# SD_SC.net
KiCad netlist of a schematic drawn in Altium Designer
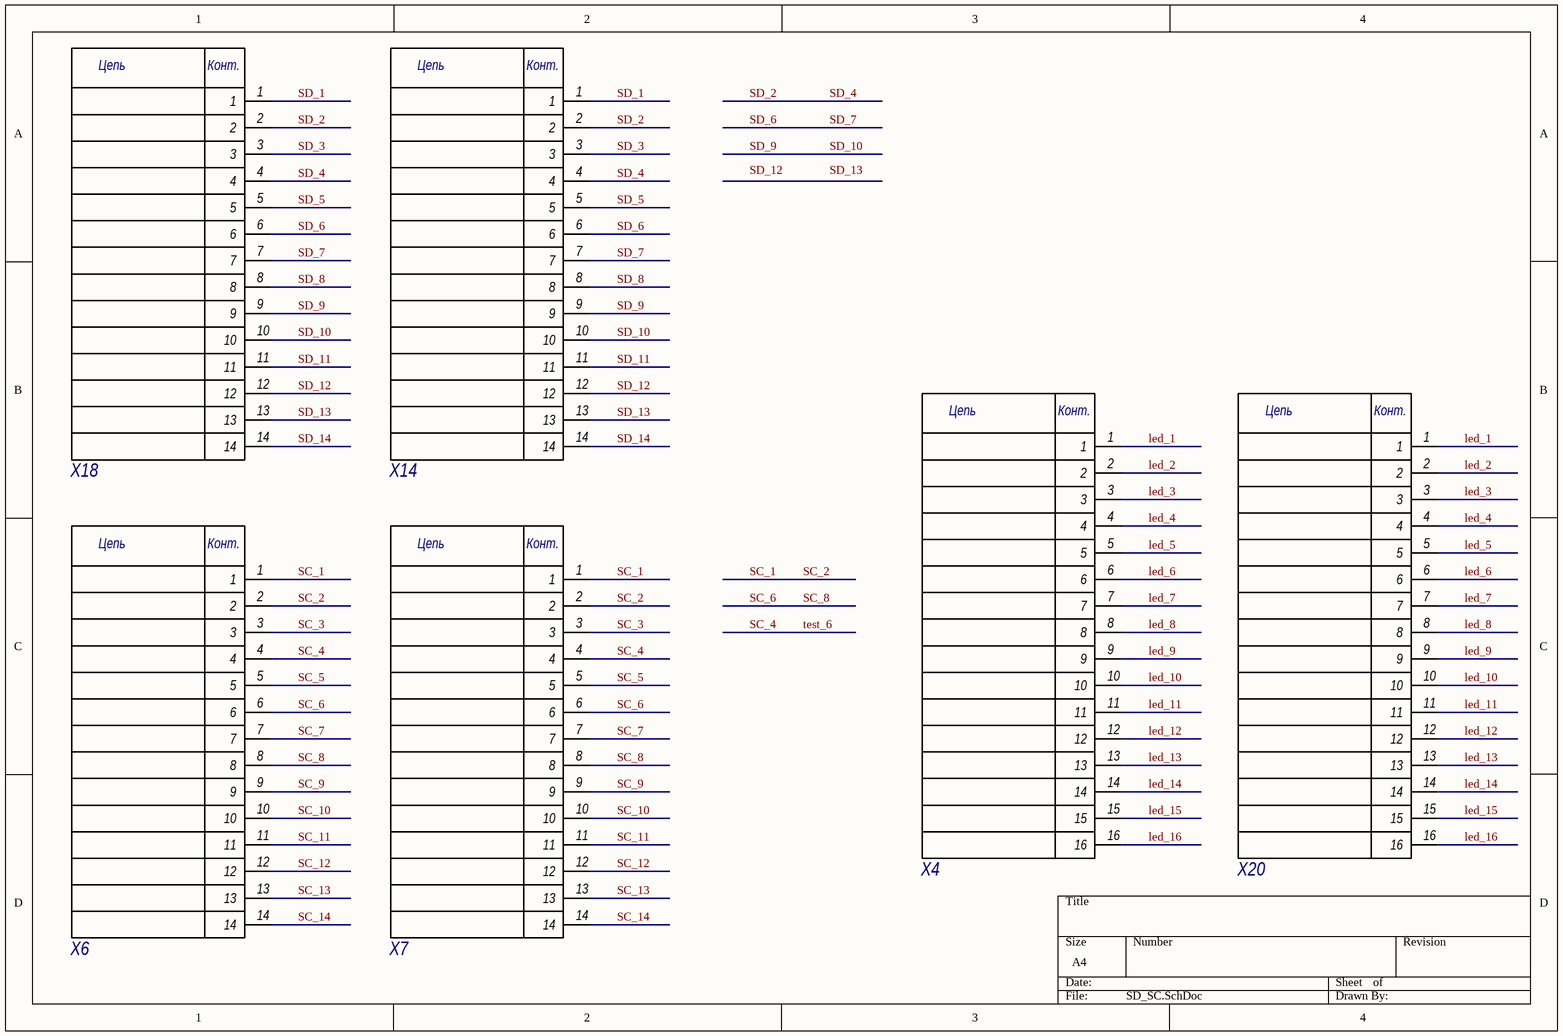
[diagram p0: SD_SC.SchDoc]

(export (version "E")
  (design (tool "Eeschema 10.0.6"))
  (components
    (comp (ref "X4")
      (value "PLD-16")
      (footprint "PLD-16")
      (description "штыри на плату")
      (libsource (lib "DatabaseSVN") (part "CON_16"))
    )
    (comp (ref "X6")
      (value "2x7")
      (footprint "87832_1420")
      (description "Connector Header Surface Mount 14 position 0.079\" (2.00mm)")
      (fields (field (name "PARTNUMBER") "87832-1420") (field (name "MANUFACTURER") "Molex"))
      (libsource (lib "DatabaseSVN") (part "CON_14"))
    )
    (comp (ref "X7")
      (value "PLD-14")
      (footprint "PLD-14")
      (description "штыри на плату")
      (libsource (lib "DatabaseSVN") (part "CON_14"))
    )
    (comp (ref "X14")
      (value "PLD-14")
      (footprint "PLD-14")
      (description "штыри на плату")
      (libsource (lib "DatabaseSVN") (part "CON_14"))
    )
    (comp (ref "X18")
      (value "2x7")
      (footprint "87832_1420")
      (description "Connector Header Surface Mount 14 position 0.079\" (2.00mm)")
      (fields (field (name "PARTNUMBER") "87832-1420") (field (name "MANUFACTURER") "Molex"))
      (libsource (lib "DatabaseSVN") (part "CON_14"))
    )
    (comp (ref "X20")
      (value "2x7")
      (footprint "87832_1620")
      (description "Connector Header Surface Mount 16 position 0.079\" (2.00mm)")
      (fields (field (name "PARTNUMBER") "87832-1620") (field (name "MANUFACTURER") "Molex"))
      (libsource (lib "DatabaseSVN") (part "CON_16"))
    )
  )
  (nets
    (net (code "1") (name "/SC_1") (class "Default")
      (node (ref "X6") (pin "1") (pinfunction "1_1") (pintype "passive"))
      (node (ref "X6") (pin "2") (pinfunction "2_2") (pintype "passive"))
      (node (ref "X7") (pin "1") (pinfunction "1_1") (pintype "passive"))
      (node (ref "X7") (pin "2") (pinfunction "2_2") (pintype "passive"))
    )
    (net (code "2") (name "/SC_3") (class "Default")
      (node (ref "X6") (pin "3") (pinfunction "3_3") (pintype "passive"))
      (node (ref "X7") (pin "3") (pinfunction "3_3") (pintype "passive"))
    )
    (net (code "3") (name "/SC_4") (class "Default")
      (node (ref "X6") (pin "4") (pinfunction "4_4") (pintype "passive"))
      (node (ref "X7") (pin "4") (pinfunction "4_4") (pintype "passive"))
    )
    (net (code "4") (name "/SC_5") (class "Default")
      (node (ref "X6") (pin "5") (pinfunction "5_5") (pintype "passive"))
      (node (ref "X7") (pin "5") (pinfunction "5_5") (pintype "passive"))
    )
    (net (code "5") (name "/SC_6") (class "Default")
      (node (ref "X6") (pin "6") (pinfunction "6_6") (pintype "passive"))
      (node (ref "X6") (pin "8") (pinfunction "8_8") (pintype "passive"))
      (node (ref "X7") (pin "6") (pinfunction "6_6") (pintype "passive"))
      (node (ref "X7") (pin "8") (pinfunction "8_8") (pintype "passive"))
    )
    (net (code "6") (name "/SC_7") (class "Default")
      (node (ref "X6") (pin "7") (pinfunction "7_7") (pintype "passive"))
      (node (ref "X7") (pin "7") (pinfunction "7_7") (pintype "passive"))
    )
    (net (code "7") (name "/SC_9") (class "Default")
      (node (ref "X6") (pin "9") (pinfunction "9_9") (pintype "passive"))
      (node (ref "X7") (pin "9") (pinfunction "9_9") (pintype "passive"))
    )
    (net (code "8") (name "/SC_10") (class "Default")
      (node (ref "X6") (pin "10") (pinfunction "10_10") (pintype "passive"))
      (node (ref "X7") (pin "10") (pinfunction "10_10") (pintype "passive"))
    )
    (net (code "9") (name "/SC_11") (class "Default")
      (node (ref "X6") (pin "11") (pinfunction "11_11") (pintype "passive"))
      (node (ref "X7") (pin "11") (pinfunction "11_11") (pintype "passive"))
    )
    (net (code "10") (name "/SC_12") (class "Default")
      (node (ref "X6") (pin "12") (pinfunction "12_12") (pintype "passive"))
      (node (ref "X7") (pin "12") (pinfunction "12_12") (pintype "passive"))
    )
    (net (code "11") (name "/SC_13") (class "Default")
      (node (ref "X6") (pin "13") (pinfunction "13_13") (pintype "passive"))
      (node (ref "X7") (pin "13") (pinfunction "13_13") (pintype "passive"))
    )
    (net (code "12") (name "/SC_14") (class "Default")
      (node (ref "X6") (pin "14") (pinfunction "14_14") (pintype "passive"))
      (node (ref "X7") (pin "14") (pinfunction "14_14") (pintype "passive"))
    )
    (net (code "13") (name "/SD_1") (class "Default")
      (node (ref "X14") (pin "1") (pinfunction "1_1") (pintype "passive"))
      (node (ref "X18") (pin "1") (pinfunction "1_1") (pintype "passive"))
    )
    (net (code "14") (name "/SD_2") (class "Default")
      (node (ref "X14") (pin "2") (pinfunction "2_2") (pintype "passive"))
      (node (ref "X14") (pin "4") (pinfunction "4_4") (pintype "passive"))
      (node (ref "X18") (pin "2") (pinfunction "2_2") (pintype "passive"))
      (node (ref "X18") (pin "4") (pinfunction "4_4") (pintype "passive"))
    )
    (net (code "15") (name "/SD_3") (class "Default")
      (node (ref "X14") (pin "3") (pinfunction "3_3") (pintype "passive"))
      (node (ref "X18") (pin "3") (pinfunction "3_3") (pintype "passive"))
    )
    (net (code "16") (name "/SD_5") (class "Default")
      (node (ref "X14") (pin "5") (pinfunction "5_5") (pintype "passive"))
      (node (ref "X18") (pin "5") (pinfunction "5_5") (pintype "passive"))
    )
    (net (code "17") (name "/SD_6") (class "Default")
      (node (ref "X14") (pin "6") (pinfunction "6_6") (pintype "passive"))
      (node (ref "X14") (pin "7") (pinfunction "7_7") (pintype "passive"))
      (node (ref "X18") (pin "6") (pinfunction "6_6") (pintype "passive"))
      (node (ref "X18") (pin "7") (pinfunction "7_7") (pintype "passive"))
    )
    (net (code "18") (name "/SD_8") (class "Default")
      (node (ref "X14") (pin "8") (pinfunction "8_8") (pintype "passive"))
      (node (ref "X18") (pin "8") (pinfunction "8_8") (pintype "passive"))
    )
    (net (code "19") (name "/SD_10") (class "Default")
      (node (ref "X14") (pin "10") (pinfunction "10_10") (pintype "passive"))
      (node (ref "X14") (pin "9") (pinfunction "9_9") (pintype "passive"))
      (node (ref "X18") (pin "10") (pinfunction "10_10") (pintype "passive"))
      (node (ref "X18") (pin "9") (pinfunction "9_9") (pintype "passive"))
    )
    (net (code "20") (name "/SD_11") (class "Default")
      (node (ref "X14") (pin "11") (pinfunction "11_11") (pintype "passive"))
      (node (ref "X18") (pin "11") (pinfunction "11_11") (pintype "passive"))
    )
    (net (code "21") (name "/SD_12") (class "Default")
      (node (ref "X14") (pin "12") (pinfunction "12_12") (pintype "passive"))
      (node (ref "X18") (pin "12") (pinfunction "12_12") (pintype "passive"))
    )
    (net (code "22") (name "/SD_13") (class "Default")
      (node (ref "X14") (pin "13") (pinfunction "13_13") (pintype "passive"))
      (node (ref "X18") (pin "13") (pinfunction "13_13") (pintype "passive"))
    )
    (net (code "23") (name "/SD_14") (class "Default")
      (node (ref "X14") (pin "14") (pinfunction "14_14") (pintype "passive"))
      (node (ref "X18") (pin "14") (pinfunction "14_14") (pintype "passive"))
    )
    (net (code "24") (name "/led_1") (class "Default")
      (node (ref "X20") (pin "1") (pinfunction "1_1") (pintype "passive"))
      (node (ref "X4") (pin "1") (pinfunction "1_1") (pintype "passive"))
    )
    (net (code "25") (name "/led_2") (class "Default")
      (node (ref "X20") (pin "2") (pinfunction "2_2") (pintype "passive"))
      (node (ref "X4") (pin "2") (pinfunction "2_2") (pintype "passive"))
    )
    (net (code "26") (name "/led_3") (class "Default")
      (node (ref "X20") (pin "3") (pinfunction "3_3") (pintype "passive"))
      (node (ref "X4") (pin "3") (pinfunction "3_3") (pintype "passive"))
    )
    (net (code "27") (name "/led_4") (class "Default")
      (node (ref "X20") (pin "4") (pinfunction "4_4") (pintype "passive"))
      (node (ref "X4") (pin "4") (pinfunction "4_4") (pintype "passive"))
    )
    (net (code "28") (name "/led_5") (class "Default")
      (node (ref "X20") (pin "5") (pinfunction "5_5") (pintype "passive"))
      (node (ref "X4") (pin "5") (pinfunction "5_5") (pintype "passive"))
    )
    (net (code "29") (name "/led_6") (class "Default")
      (node (ref "X20") (pin "6") (pinfunction "6_6") (pintype "passive"))
      (node (ref "X4") (pin "6") (pinfunction "6_6") (pintype "passive"))
    )
    (net (code "30") (name "/led_7") (class "Default")
      (node (ref "X20") (pin "7") (pinfunction "7_7") (pintype "passive"))
      (node (ref "X4") (pin "7") (pinfunction "7_7") (pintype "passive"))
    )
    (net (code "31") (name "/led_8") (class "Default")
      (node (ref "X20") (pin "8") (pinfunction "8_8") (pintype "passive"))
      (node (ref "X4") (pin "8") (pinfunction "8_8") (pintype "passive"))
    )
    (net (code "32") (name "/led_9") (class "Default")
      (node (ref "X20") (pin "9") (pinfunction "9_9") (pintype "passive"))
      (node (ref "X4") (pin "9") (pinfunction "9_9") (pintype "passive"))
    )
    (net (code "33") (name "/led_10") (class "Default")
      (node (ref "X20") (pin "10") (pinfunction "10_10") (pintype "passive"))
      (node (ref "X4") (pin "10") (pinfunction "10_10") (pintype "passive"))
    )
    (net (code "34") (name "/led_11") (class "Default")
      (node (ref "X20") (pin "11") (pinfunction "11_11") (pintype "passive"))
      (node (ref "X4") (pin "11") (pinfunction "11_11") (pintype "passive"))
    )
    (net (code "35") (name "/led_12") (class "Default")
      (node (ref "X20") (pin "12") (pinfunction "12_12") (pintype "passive"))
      (node (ref "X4") (pin "12") (pinfunction "12_12") (pintype "passive"))
    )
    (net (code "36") (name "/led_13") (class "Default")
      (node (ref "X20") (pin "13") (pinfunction "13_13") (pintype "passive"))
      (node (ref "X4") (pin "13") (pinfunction "13_13") (pintype "passive"))
    )
    (net (code "37") (name "/led_14") (class "Default")
      (node (ref "X20") (pin "14") (pinfunction "14_14") (pintype "passive"))
      (node (ref "X4") (pin "14") (pinfunction "14_14") (pintype "passive"))
    )
    (net (code "38") (name "/led_15") (class "Default")
      (node (ref "X20") (pin "15") (pinfunction "15_15") (pintype "passive"))
      (node (ref "X4") (pin "15") (pinfunction "15_15") (pintype "passive"))
    )
    (net (code "39") (name "/led_16") (class "Default")
      (node (ref "X20") (pin "16") (pinfunction "16_16") (pintype "passive"))
      (node (ref "X4") (pin "16") (pinfunction "16_16") (pintype "passive"))
    )
  )
)
